# p2b-001.net
KiCad netlist of a schematic drawn in EAGLE
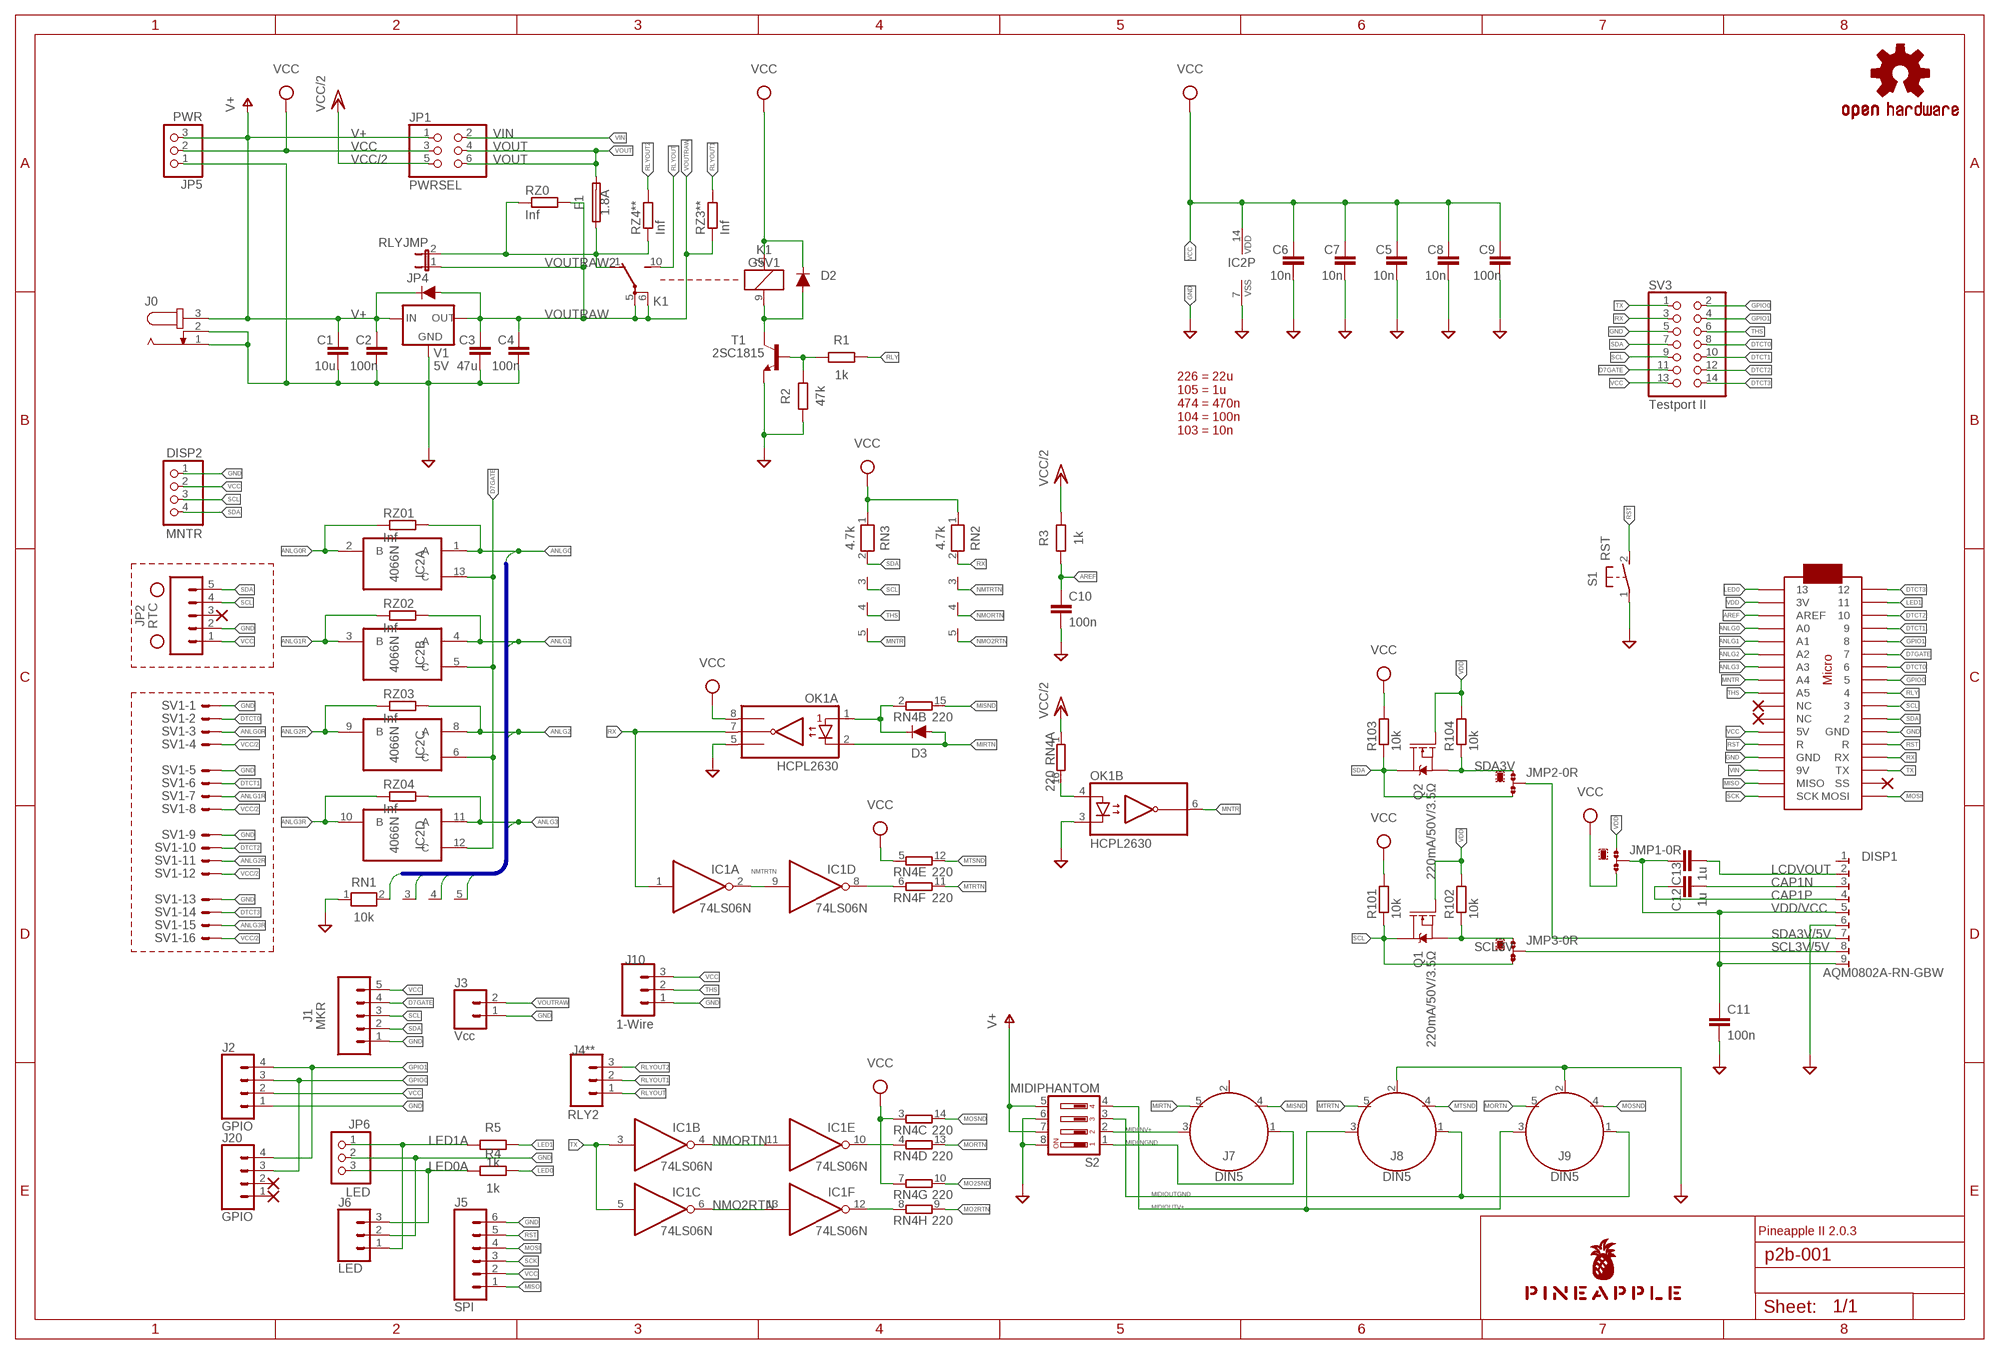
[diagram p0: schematic, sheet 1]

(export (version "E")
  (design (tool "Eeschema 10.0.6"))
  (components
    (comp (ref "C1")
      (value "10u")
      (footprint "eagle-import:C025-030X050")
      (libsource (lib "eagle-import") (part "C-EU025-030X050"))
    )
    (comp (ref "C2")
      (value "100n")
      (footprint "eagle-import:C025-024X044")
      (libsource (lib "eagle-import") (part "C-EU025-024X044"))
    )
    (comp (ref "C3")
      (value "47u")
      (footprint "eagle-import:C025-050X050")
      (libsource (lib "eagle-import") (part "C-EU025-050X050"))
    )
    (comp (ref "C4")
      (value "100n")
      (footprint "eagle-import:C025-024X044")
      (libsource (lib "eagle-import") (part "C-EU025-024X044"))
    )
    (comp (ref "C5")
      (value "10n")
      (footprint "eagle-import:C025-024X044")
      (libsource (lib "eagle-import") (part "resistor_348_C-EU025-024X044"))
    )
    (comp (ref "C6")
      (value "10n")
      (footprint "eagle-import:C025-024X044")
      (libsource (lib "eagle-import") (part "resistor_348_C-EU025-024X044"))
    )
    (comp (ref "C7")
      (value "10n")
      (footprint "eagle-import:C025-024X044")
      (libsource (lib "eagle-import") (part "resistor_348_C-EU025-024X044"))
    )
    (comp (ref "C8")
      (value "10n")
      (footprint "eagle-import:C025-024X044")
      (libsource (lib "eagle-import") (part "resistor_348_C-EU025-024X044"))
    )
    (comp (ref "C9")
      (value "100n")
      (footprint "eagle-import:C025-024X044")
      (libsource (lib "eagle-import") (part "resistor_348_C-EU025-024X044"))
    )
    (comp (ref "C10")
      (value "100n")
      (footprint "eagle-import:C025-024X044")
      (libsource (lib "eagle-import") (part "C-EU025-024X044"))
    )
    (comp (ref "C11")
      (value "100n")
      (footprint "eagle-import:C025-024X044")
      (libsource (lib "eagle-import") (part "C-EU025-024X044"))
    )
    (comp (ref "C12")
      (value "1u")
      (footprint "eagle-import:C050-024X044")
      (libsource (lib "eagle-import") (part "C-EU050-024X044"))
    )
    (comp (ref "C13")
      (value "1u")
      (footprint "eagle-import:C050-024X044")
      (libsource (lib "eagle-import") (part "C-EU050-024X044"))
    )
    (comp (ref "D1")
      (value "DIODE-1N4148")
      (footprint "eagle-import:DIODE-1N4148")
      (libsource (lib "eagle-import") (part "DIODE-1N4148"))
    )
    (comp (ref "D2")
      (value "DIODE-1N4148")
      (footprint "eagle-import:DIODE-1N4148")
      (libsource (lib "eagle-import") (part "DIODE-1N4148"))
    )
    (comp (ref "D3")
      (value "DIODE-1N4148")
      (footprint "eagle-import:DIODE-1N4148")
      (libsource (lib "eagle-import") (part "DIODE-1N4148"))
    )
    (comp (ref "DISP1")
      (value "AQM0802A-RN-GBW")
      (footprint "eagle-import:AQM0802A-RN-GBW-FOOTPRINT")
      (libsource (lib "eagle-import") (part "AQM0802A-RN-GBW"))
    )
    (comp (ref "DISP2")
      (value "MNTR")
      (footprint "eagle-import:1X04")
      (libsource (lib "eagle-import") (part "PINHD-1X4"))
    )
    (comp (ref "F1")
      (value "1.8A")
      (footprint "eagle-import:TE5")
      (libsource (lib "eagle-import") (part "TE5"))
    )
    (comp (ref "H1")
      (value "STAND-OFF")
      (footprint "eagle-import:STAND-OFF")
      (libsource (lib "eagle-import") (part "STAND-OFF"))
    )
    (comp (ref "H2")
      (value "STAND-OFF")
      (footprint "eagle-import:STAND-OFF")
      (libsource (lib "eagle-import") (part "STAND-OFF"))
    )
    (comp (ref "IC1")
      (value "74LS06N")
      (footprint "eagle-import:DIL14")
      (libsource (lib "eagle-import") (part "7406NLS"))
    )
    (comp (ref "IC2")
      (value "4066N")
      (footprint "eagle-import:DIL14")
      (libsource (lib "eagle-import") (part "4066N"))
    )
    (comp (ref "J0")
      (value "JACK-PLUG0")
      (footprint "eagle-import:SPC4077")
      (libsource (lib "eagle-import") (part "JACK-PLUG0"))
    )
    (comp (ref "J1")
      (value "MKR")
      (footprint "eagle-import:JST-5-PTH")
      (libsource (lib "eagle-import") (part "CONN_05JST"))
    )
    (comp (ref "J2")
      (value "GPIO")
      (footprint "eagle-import:JST-4-PTH")
      (libsource (lib "eagle-import") (part "CONN_04JST-PTH"))
    )
    (comp (ref "J3")
      (value "Vcc")
      (footprint "eagle-import:JST-2-PTH")
      (libsource (lib "eagle-import") (part "CONN_02JST-PTH-2"))
    )
    (comp (ref "J4**")
      (value "RLY2")
      (footprint "eagle-import:JST-3-PTH-NS")
      (libsource (lib "eagle-import") (part "CONN_03JST-PTH-NS"))
    )
    (comp (ref "J5")
      (value "SPI")
      (footprint "eagle-import:1X06_1.27MM")
      (libsource (lib "eagle-import") (part "CONN_061.27MM"))
    )
    (comp (ref "J6")
      (value "LED")
      (footprint "eagle-import:JST-3-PTH-VERT")
      (libsource (lib "eagle-import") (part "CONN_03JST-PTH-VERT"))
    )
    (comp (ref "J7")
      (value "DIN5")
      (footprint "eagle-import:DIN5-RA-PTH")
      (libsource (lib "eagle-import") (part "DIN5"))
    )
    (comp (ref "J8")
      (value "DIN5")
      (footprint "eagle-import:DIN5-RA-PTH")
      (libsource (lib "eagle-import") (part "DIN5"))
    )
    (comp (ref "J9")
      (value "DIN5")
      (footprint "eagle-import:DIN5-RA-PTH")
      (libsource (lib "eagle-import") (part "DIN5"))
    )
    (comp (ref "J10")
      (value "1-Wire")
      (footprint "eagle-import:JST-3-PTH-VERT")
      (libsource (lib "eagle-import") (part "CONN_03JST-PTH-VERT"))
    )
    (comp (ref "J20")
      (value "GPIO")
      (footprint "eagle-import:1X04_1.27MM")
      (libsource (lib "eagle-import") (part "CONN_041.27MM"))
    )
    (comp (ref "JMP1")
      (value "0R-JUMPA")
      (footprint "eagle-import:A0R-JMP")
      (libsource (lib "eagle-import") (part "0R-JUMPA"))
    )
    (comp (ref "JMP2")
      (value "0R-JUMPA")
      (footprint "eagle-import:A0R-JMP")
      (libsource (lib "eagle-import") (part "0R-JUMPA"))
    )
    (comp (ref "JMP3")
      (value "0R-JUMPA")
      (footprint "eagle-import:A0R-JMP")
      (libsource (lib "eagle-import") (part "0R-JUMPA"))
    )
    (comp (ref "JP1")
      (value "PWRSEL")
      (footprint "eagle-import:2X03")
      (libsource (lib "eagle-import") (part "PINHD-2X3"))
    )
    (comp (ref "JP2")
      (value "RTC")
      (footprint "eagle-import:1X05")
      (libsource (lib "eagle-import") (part "CONN_05"))
    )
    (comp (ref "JP4")
      (value "RLYJMP")
      (footprint "eagle-import:JP1")
      (libsource (lib "eagle-import") (part "JP1E"))
    )
    (comp (ref "JP5")
      (value "PWR")
      (footprint "eagle-import:1X03")
      (libsource (lib "eagle-import") (part "PINHD-1X3"))
    )
    (comp (ref "JP6")
      (value "LED")
      (footprint "eagle-import:1X03")
      (libsource (lib "eagle-import") (part "PINHD-1X3"))
    )
    (comp (ref "K1")
      (value "G5V1")
      (footprint "eagle-import:G5V1")
      (fields (field (name "MPN") "G5V-1-DC24"))
      (libsource (lib "eagle-import") (part "G5V1"))
    )
    (comp (ref "LOGO1")
      (value "OSHW-LOGOS-COPPER")
      (footprint "eagle-import:OSHW-LOGO-S_COPPER")
      (libsource (lib "eagle-import") (part "OSHW-LOGOS-COPPER"))
    )
    (comp (ref "MC1")
      (value "ARDUINOMICRO")
      (footprint "eagle-import:ARDUINOMICRO")
      (libsource (lib "eagle-import") (part "ARDUINOMICRO"))
    )
    (comp (ref "OK1")
      (value "HCPL2630")
      (footprint "eagle-import:DIL08")
      (fields (field (name "MF") "AGILENT TECHNOLOGIES") (field (name "MPN") "HCPL-2630-000E"))
      (libsource (lib "eagle-import") (part "HCPL2630"))
    )
    (comp (ref "Q1")
      (value "220mA/50V/3.5Ω")
      (footprint "eagle-import:SOT23-3")
      (libsource (lib "eagle-import") (part "MOSFET-NCH-BSS138"))
    )
    (comp (ref "Q2")
      (value "220mA/50V/3.5Ω")
      (footprint "eagle-import:SOT23-3")
      (libsource (lib "eagle-import") (part "MOSFET-NCH-BSS138"))
    )
    (comp (ref "R1")
      (value "1k")
      (footprint "eagle-import:0204_5")
      (libsource (lib "eagle-import") (part "resistor_348_R-EU_0204/5"))
    )
    (comp (ref "R2")
      (value "47k")
      (footprint "eagle-import:0204_5")
      (libsource (lib "eagle-import") (part "resistor_348_R-EU_0204/5"))
    )
    (comp (ref "R3")
      (value "1k")
      (footprint "eagle-import:0204_5")
      (libsource (lib "eagle-import") (part "resistor_348_R-EU_0204/5"))
    )
    (comp (ref "R4")
      (value "1k")
      (footprint "eagle-import:0204_5")
      (libsource (lib "eagle-import") (part "resistor_348_R-EU_0204/5"))
    )
    (comp (ref "R5")
      (value "1k")
      (footprint "eagle-import:0204_5")
      (libsource (lib "eagle-import") (part "resistor_348_R-EU_0204/5"))
    )
    (comp (ref "R101")
      (value "10k")
      (footprint "eagle-import:M2012")
      (libsource (lib "eagle-import") (part "R-EU_M2012"))
    )
    (comp (ref "R102")
      (value "10k")
      (footprint "eagle-import:M2012")
      (libsource (lib "eagle-import") (part "R-EU_M2012"))
    )
    (comp (ref "R103")
      (value "10k")
      (footprint "eagle-import:M2012")
      (libsource (lib "eagle-import") (part "R-EU_M2012"))
    )
    (comp (ref "R104")
      (value "10k")
      (footprint "eagle-import:M2012")
      (libsource (lib "eagle-import") (part "R-EU_M2012"))
    )
    (comp (ref "RN1")
      (value "10k")
      (footprint "eagle-import:RN-5")
      (libsource (lib "eagle-import") (part "RN04"))
    )
    (comp (ref "RN2")
      (value "4.7k")
      (footprint "eagle-import:RN-5")
      (libsource (lib "eagle-import") (part "RN04"))
    )
    (comp (ref "RN3")
      (value "4.7k")
      (footprint "eagle-import:RN-5")
      (libsource (lib "eagle-import") (part "RN04"))
    )
    (comp (ref "RN4")
      (value "220")
      (footprint "eagle-import:DIL16")
      (libsource (lib "eagle-import") (part "8R-N"))
    )
    (comp (ref "RZ0")
      (value "Inf")
      (footprint "eagle-import:M2012")
      (libsource (lib "eagle-import") (part "R-EU_M2012"))
    )
    (comp (ref "RZ01")
      (value "Inf")
      (footprint "eagle-import:M2012")
      (libsource (lib "eagle-import") (part "R-EU_M2012"))
    )
    (comp (ref "RZ02")
      (value "Inf")
      (footprint "eagle-import:M2012")
      (libsource (lib "eagle-import") (part "R-EU_M2012"))
    )
    (comp (ref "RZ03")
      (value "Inf")
      (footprint "eagle-import:M2012")
      (libsource (lib "eagle-import") (part "R-EU_M2012"))
    )
    (comp (ref "RZ3**")
      (value "Inf")
      (footprint "eagle-import:M2012")
      (libsource (lib "eagle-import") (part "R-EU_M2012"))
    )
    (comp (ref "RZ04")
      (value "Inf")
      (footprint "eagle-import:M2012")
      (libsource (lib "eagle-import") (part "R-EU_M2012"))
    )
    (comp (ref "RZ4**")
      (value "Inf")
      (footprint "eagle-import:M2012")
      (libsource (lib "eagle-import") (part "R-EU_M2012"))
    )
    (comp (ref "S1")
      (value "RST")
      (footprint "eagle-import:B3F-31XX")
      (fields (field (name "MPN") "B3F-3100"))
      (libsource (lib "eagle-import") (part "31-XX"))
    )
    (comp (ref "S2")
      (value "MIDIPHANTOM")
      (footprint "eagle-import:DIP04YL")
      (libsource (lib "eagle-import") (part "DIP04YL"))
    )
    (comp (ref "SV1")
      (value "ML16LE")
      (footprint "eagle-import:ML16L")
      (libsource (lib "eagle-import") (part "ML16LE"))
    )
    (comp (ref "SV3")
      (value "Testport II")
      (footprint "eagle-import:2X07")
      (libsource (lib "eagle-import") (part "PINHD-2X7"))
    )
    (comp (ref "T1")
      (value "2SC1815")
      (footprint "eagle-import:TO92-ECB")
      (libsource (lib "eagle-import") (part "2SC1815"))
    )
    (comp (ref "U$1")
      (value "PINEAPPLE450_SILK")
      (footprint "eagle-import:PINEAPPLE450_SILK")
      (libsource (lib "eagle-import") (part "PINEAPPLE450_SILK"))
    )
    (comp (ref "V1")
      (value "5V")
      (footprint "eagle-import:78XXS")
      (libsource (lib "eagle-import") (part "78XXS"))
    )
  )
  (nets
    (net (code "1") (name "/CAP1N") (class "Default")
      (node (ref "C12") (pin "2") (pinfunction "2_2") (pintype "passive"))
      (node (ref "DISP1") (pin "3") (pinfunction "3_3") (pintype "passive"))
    )
    (net (code "2") (name "/CAP1P") (class "Default")
      (node (ref "C12") (pin "1") (pinfunction "1_1") (pintype "passive"))
      (node (ref "DISP1") (pin "4") (pinfunction "4_4") (pintype "passive"))
    )
    (net (code "3") (name "/LCDVOUT") (class "Default")
      (node (ref "C13") (pin "2") (pinfunction "2_2") (pintype "passive"))
      (node (ref "DISP1") (pin "2") (pinfunction "2_2") (pintype "passive"))
    )
    (net (code "4") (name "/LED0A") (class "Default")
      (node (ref "J6") (pin "3") (pinfunction "3_3") (pintype "passive"))
      (node (ref "JP6") (pin "3") (pinfunction "3_3") (pintype "passive"))
      (node (ref "R4") (pin "1") (pinfunction "1_1") (pintype "passive"))
    )
    (net (code "5") (name "/LED1A") (class "Default")
      (node (ref "J6") (pin "1") (pinfunction "1_1") (pintype "passive"))
      (node (ref "JP6") (pin "1") (pinfunction "1_1") (pintype "passive"))
      (node (ref "R5") (pin "1") (pinfunction "1_1") (pintype "passive"))
    )
    (net (code "6") (name "/MIDIINGND") (class "Default")
      (node (ref "J7") (pin "1") (pinfunction "1_1") (pintype "bidirectional"))
      (node (ref "S2") (pin "1") (pinfunction "1_1") (pintype "passive"))
    )
    (net (code "7") (name "/MIDIINV+") (class "Default")
      (node (ref "J7") (pin "3") (pinfunction "3_3") (pintype "bidirectional"))
      (node (ref "S2") (pin "2") (pinfunction "2_2") (pintype "passive"))
    )
    (net (code "8") (name "/MIDIOUTGND") (class "Default")
      (node (ref "J8") (pin "1") (pinfunction "1_1") (pintype "bidirectional"))
      (node (ref "J9") (pin "1") (pinfunction "1_1") (pintype "bidirectional"))
      (node (ref "S2") (pin "3") (pinfunction "3_3") (pintype "passive"))
    )
    (net (code "9") (name "/MIDIOUTV+") (class "Default")
      (node (ref "J8") (pin "3") (pinfunction "3_3") (pintype "bidirectional"))
      (node (ref "J9") (pin "3") (pinfunction "3_3") (pintype "bidirectional"))
      (node (ref "S2") (pin "4") (pinfunction "4_4") (pintype "passive"))
    )
    (net (code "10") (name "/SCL3V") (class "Default")
      (node (ref "JMP3") (pin "1") (pinfunction "1_1") (pintype "passive"))
      (node (ref "Q1") (pin "2") (pinfunction "S_2") (pintype "bidirectional"))
      (node (ref "R102") (pin "1") (pinfunction "1_1") (pintype "passive"))
    )
    (net (code "11") (name "/SCL3V{slash}5V") (class "Default")
      (node (ref "DISP1") (pin "8") (pinfunction "8_8") (pintype "passive"))
      (node (ref "JMP3") (pin "2") (pinfunction "2_2") (pintype "passive"))
    )
    (net (code "12") (name "/SDA3V") (class "Default")
      (node (ref "JMP2") (pin "1") (pinfunction "1_1") (pintype "passive"))
      (node (ref "Q2") (pin "2") (pinfunction "S_2") (pintype "bidirectional"))
      (node (ref "R104") (pin "1") (pinfunction "1_1") (pintype "passive"))
    )
    (net (code "13") (name "/SDA3V{slash}5V") (class "Default")
      (node (ref "DISP1") (pin "7") (pinfunction "7_7") (pintype "passive"))
      (node (ref "JMP2") (pin "2") (pinfunction "2_2") (pintype "passive"))
    )
    (net (code "14") (name "/VDD{slash}VCC") (class "Default")
      (node (ref "C11") (pin "1") (pinfunction "1_1") (pintype "passive"))
      (node (ref "C13") (pin "1") (pinfunction "1_1") (pintype "passive"))
      (node (ref "DISP1") (pin "5") (pinfunction "5_5") (pintype "passive"))
      (node (ref "DISP1") (pin "9") (pinfunction "9_9") (pintype "passive"))
      (node (ref "JMP1") (pin "2") (pinfunction "2_2") (pintype "passive"))
    )
    (net (code "15") (name "/VOUTRAW2") (class "Default")
      (node (ref "F1") (pin "1") (pinfunction "1_1") (pintype "passive"))
      (node (ref "JP4") (pin "2") (pinfunction "2_2") (pintype "passive"))
      (node (ref "K1") (pin "1") (pinfunction "O_1") (pintype "passive"))
      (node (ref "RZ0") (pin "1") (pinfunction "1_1") (pintype "passive"))
      (node (ref "RZ4**") (pin "1") (pinfunction "1_1") (pintype "passive"))
    )
    (net (code "16") (name "ANLG0") (class "Default")
      (node (ref "IC2") (pin "1") (pinfunction "A_1") (pintype "tri_state"))
      (node (ref "MC1") (pin "P$31") (pinfunction "A0_P$31") (pintype "bidirectional"))
      (node (ref "RN1") (pin "2") (pinfunction "2_2") (pintype "passive"))
      (node (ref "RZ01") (pin "2") (pinfunction "2_2") (pintype "passive"))
    )
    (net (code "17") (name "ANLG0R") (class "Default")
      (node (ref "IC2") (pin "2") (pinfunction "B_2") (pintype "tri_state"))
      (node (ref "RZ01") (pin "1") (pinfunction "1_1") (pintype "passive"))
      (node (ref "SV1") (pin "3") (pinfunction "S_3") (pintype "passive"))
    )
    (net (code "18") (name "ANLG1") (class "Default")
      (node (ref "IC2") (pin "4") (pinfunction "A_4") (pintype "tri_state"))
      (node (ref "MC1") (pin "P$30") (pinfunction "A1_P$30") (pintype "bidirectional"))
      (node (ref "RN1") (pin "3") (pinfunction "3_3") (pintype "passive"))
      (node (ref "RZ02") (pin "2") (pinfunction "2_2") (pintype "passive"))
    )
    (net (code "19") (name "ANLG1R") (class "Default")
      (node (ref "IC2") (pin "3") (pinfunction "B_3") (pintype "tri_state"))
      (node (ref "RZ02") (pin "1") (pinfunction "1_1") (pintype "passive"))
      (node (ref "SV1") (pin "7") (pinfunction "S_7") (pintype "passive"))
    )
    (net (code "20") (name "ANLG2") (class "Default")
      (node (ref "IC2") (pin "8") (pinfunction "A_8") (pintype "tri_state"))
      (node (ref "MC1") (pin "P$29") (pinfunction "A2_P$29") (pintype "bidirectional"))
      (node (ref "RN1") (pin "4") (pinfunction "4_4") (pintype "passive"))
      (node (ref "RZ03") (pin "2") (pinfunction "2_2") (pintype "passive"))
    )
    (net (code "21") (name "ANLG2R") (class "Default")
      (node (ref "IC2") (pin "9") (pinfunction "B_9") (pintype "tri_state"))
      (node (ref "RZ03") (pin "1") (pinfunction "1_1") (pintype "passive"))
      (node (ref "SV1") (pin "11") (pinfunction "S_11") (pintype "passive"))
    )
    (net (code "22") (name "ANLG3") (class "Default")
      (node (ref "IC2") (pin "11") (pinfunction "A_11") (pintype "tri_state"))
      (node (ref "MC1") (pin "P$28") (pinfunction "A3_P$28") (pintype "bidirectional"))
      (node (ref "RN1") (pin "5") (pinfunction "5_5") (pintype "passive"))
      (node (ref "RZ04") (pin "2") (pinfunction "2_2") (pintype "passive"))
    )
    (net (code "23") (name "ANLG3R") (class "Default")
      (node (ref "IC2") (pin "10") (pinfunction "B_10") (pintype "tri_state"))
      (node (ref "RZ04") (pin "1") (pinfunction "1_1") (pintype "passive"))
      (node (ref "SV1") (pin "15") (pinfunction "S_15") (pintype "passive"))
    )
    (net (code "24") (name "AREF") (class "Default")
      (node (ref "C10") (pin "1") (pinfunction "1_1") (pintype "passive"))
      (node (ref "MC1") (pin "P$32") (pinfunction "AREF_P$32") (pintype "bidirectional"))
      (node (ref "R3") (pin "1") (pinfunction "1_1") (pintype "passive"))
    )
    (net (code "25") (name "D7GATE") (class "Default")
      (node (ref "IC2") (pin "12") (pinfunction "C_12") (pintype "input"))
      (node (ref "IC2") (pin "13") (pinfunction "C_13") (pintype "input"))
      (node (ref "IC2") (pin "5") (pinfunction "C_5") (pintype "input"))
      (node (ref "IC2") (pin "6") (pinfunction "C_6") (pintype "input"))
      (node (ref "J1") (pin "4") (pinfunction "4_4") (pintype "passive"))
      (node (ref "MC1") (pin "P$6") (pinfunction "7_P$6") (pintype "bidirectional"))
      (node (ref "SV3") (pin "11") (pinfunction "11_11") (pintype "passive"))
    )
    (net (code "26") (name "DTCT0") (class "Default")
      (node (ref "MC1") (pin "P$7") (pinfunction "6_P$7") (pintype "bidirectional"))
      (node (ref "SV1") (pin "2") (pinfunction "S_2") (pintype "passive"))
      (node (ref "SV3") (pin "8") (pinfunction "8_8") (pintype "passive"))
    )
    (net (code "27") (name "DTCT1") (class "Default")
      (node (ref "MC1") (pin "P$4") (pinfunction "9_P$4") (pintype "bidirectional"))
      (node (ref "SV1") (pin "6") (pinfunction "S_6") (pintype "passive"))
      (node (ref "SV3") (pin "10") (pinfunction "10_10") (pintype "passive"))
    )
    (net (code "28") (name "DTCT2") (class "Default")
      (node (ref "MC1") (pin "P$3") (pinfunction "10_P$3") (pintype "bidirectional"))
      (node (ref "SV1") (pin "10") (pinfunction "S_10") (pintype "passive"))
      (node (ref "SV3") (pin "12") (pinfunction "12_12") (pintype "passive"))
    )
    (net (code "29") (name "DTCT3") (class "Default")
      (node (ref "MC1") (pin "P$1") (pinfunction "12_P$1") (pintype "bidirectional"))
      (node (ref "SV1") (pin "14") (pinfunction "S_14") (pintype "passive"))
      (node (ref "SV3") (pin "14") (pinfunction "14_14") (pintype "passive"))
    )
    (net (code "30") (name "GND") (class "Default")
      (node (ref "C1") (pin "2") (pinfunction "2_2") (pintype "passive"))
      (node (ref "C10") (pin "2") (pinfunction "2_2") (pintype "passive"))
      (node (ref "C11") (pin "2") (pinfunction "2_2") (pintype "passive"))
      (node (ref "C2") (pin "2") (pinfunction "2_2") (pintype "passive"))
      (node (ref "C3") (pin "2") (pinfunction "2_2") (pintype "passive"))
      (node (ref "C4") (pin "2") (pinfunction "2_2") (pintype "passive"))
      (node (ref "C5") (pin "2") (pinfunction "2_2") (pintype "passive"))
      (node (ref "C6") (pin "2") (pinfunction "2_2") (pintype "passive"))
      (node (ref "C7") (pin "2") (pinfunction "2_2") (pintype "passive"))
      (node (ref "C8") (pin "2") (pinfunction "2_2") (pintype "passive"))
      (node (ref "C9") (pin "2") (pinfunction "2_2") (pintype "passive"))
      (node (ref "DISP1") (pin "6") (pinfunction "6_6") (pintype "passive"))
      (node (ref "DISP2") (pin "1") (pinfunction "1_1") (pintype "passive"))
      (node (ref "IC2") (pin "7") (pinfunction "VSS_7") (pintype "power_in"))
      (node (ref "J0") (pin "1") (pinfunction "1_1") (pintype "passive"))
      (node (ref "J0") (pin "2") (pinfunction "2_2") (pintype "passive"))
      (node (ref "J1") (pin "1") (pinfunction "1_1") (pintype "passive"))
      (node (ref "J10") (pin "1") (pinfunction "1_1") (pintype "passive"))
      (node (ref "J2") (pin "1") (pinfunction "1_1") (pintype "passive"))
      (node (ref "J3") (pin "1") (pinfunction "1_1") (pintype "passive"))
      (node (ref "J5") (pin "6") (pinfunction "6_6") (pintype "passive"))
      (node (ref "J6") (pin "2") (pinfunction "2_2") (pintype "passive"))
      (node (ref "J8") (pin "2") (pinfunction "2_2") (pintype "bidirectional"))
      (node (ref "J9") (pin "2") (pinfunction "2_2") (pintype "bidirectional"))
      (node (ref "JP2") (pin "2") (pinfunction "2_2") (pintype "passive"))
      (node (ref "JP5") (pin "1") (pinfunction "1_1") (pintype "passive"))
      (node (ref "JP6") (pin "2") (pinfunction "2_2") (pintype "passive"))
      (node (ref "MC1") (pin "P$12") (pinfunction "GND_P$12") (pintype "bidirectional"))
      (node (ref "MC1") (pin "P$21") (pinfunction "GND_P$21") (pintype "bidirectional"))
      (node (ref "OK1") (pin "3") (pinfunction "C2_3") (pintype "passive"))
      (node (ref "OK1") (pin "5") (pinfunction "GND_5") (pintype "passive"))
      (node (ref "R2") (pin "1") (pinfunction "1_1") (pintype "passive"))
      (node (ref "RN1") (pin "1") (pinfunction "1_1") (pintype "passive"))
      (node (ref "S1") (pin "1") (pinfunction "P_1") (pintype "passive"))
      (node (ref "S2") (pin "6") (pinfunction "6_6") (pintype "passive"))
      (node (ref "S2") (pin "8") (pinfunction "8_8") (pintype "passive"))
      (node (ref "SV1") (pin "1") (pinfunction "S_1") (pintype "passive"))
      (node (ref "SV1") (pin "13") (pinfunction "S_13") (pintype "passive"))
      (node (ref "SV1") (pin "5") (pinfunction "S_5") (pintype "passive"))
      (node (ref "SV1") (pin "9") (pinfunction "S_9") (pintype "passive"))
      (node (ref "SV3") (pin "5") (pinfunction "5_5") (pintype "passive"))
      (node (ref "T1") (pin "E") (pinfunction "E_E") (pintype "passive"))
      (node (ref "V1") (pin "GND") (pinfunction "GND_GND") (pintype "input"))
    )
    (net (code "31") (name "GPIO0") (class "Default")
      (node (ref "J2") (pin "3") (pinfunction "3_3") (pintype "passive"))
      (node (ref "J20") (pin "3") (pinfunction "3_3") (pintype "passive"))
      (node (ref "MC1") (pin "P$8") (pinfunction "5_P$8") (pintype "bidirectional"))
      (node (ref "SV3") (pin "2") (pinfunction "2_2") (pintype "passive"))
    )
    (net (code "32") (name "GPIO1") (class "Default")
      (node (ref "J2") (pin "4") (pinfunction "4_4") (pintype "passive"))
      (node (ref "J20") (pin "4") (pinfunction "4_4") (pintype "passive"))
      (node (ref "MC1") (pin "P$5") (pinfunction "8_P$5") (pintype "bidirectional"))
      (node (ref "SV3") (pin "4") (pinfunction "4_4") (pintype "passive"))
    )
    (net (code "33") (name "LED0") (class "Default")
      (node (ref "MC1") (pin "P$34") (pinfunction "13_P$34") (pintype "bidirectional"))
      (node (ref "R4") (pin "2") (pinfunction "2_2") (pintype "passive"))
    )
    (net (code "34") (name "LED1") (class "Default")
      (node (ref "MC1") (pin "P$2") (pinfunction "11_P$2") (pintype "bidirectional"))
      (node (ref "R5") (pin "2") (pinfunction "2_2") (pintype "passive"))
    )
    (net (code "35") (name "MIRTN") (class "Default")
      (node (ref "D3") (pin "A") (pinfunction "A_A") (pintype "passive"))
      (node (ref "J7") (pin "5") (pinfunction "5_5") (pintype "bidirectional"))
      (node (ref "OK1") (pin "2") (pinfunction "C1_2") (pintype "passive"))
    )
    (net (code "36") (name "MISND") (class "Default")
      (node (ref "J7") (pin "4") (pinfunction "4_4") (pintype "bidirectional"))
      (node (ref "RN4") (pin "15") (pinfunction "2_15") (pintype "passive"))
    )
    (net (code "37") (name "MISO") (class "Default")
      (node (ref "J5") (pin "1") (pinfunction "1_1") (pintype "passive"))
      (node (ref "MC1") (pin "P$19") (pinfunction "MISO_P$19") (pintype "bidirectional"))
    )
    (net (code "38") (name "MNTR") (class "Default")
      (node (ref "MC1") (pin "P$27") (pinfunction "A4_P$27") (pintype "bidirectional"))
      (node (ref "OK1") (pin "6") (pinfunction "VO2_6") (pintype "passive"))
      (node (ref "RN3") (pin "5") (pinfunction "5_5") (pintype "passive"))
    )
    (net (code "39") (name "MO2RTN") (class "Default")
      (node (ref "RN4") (pin "9") (pinfunction "2_9") (pintype "passive"))
    )
    (net (code "40") (name "MO2SND") (class "Default")
      (node (ref "RN4") (pin "10") (pinfunction "2_10") (pintype "passive"))
    )
    (net (code "41") (name "MORTN") (class "Default")
      (node (ref "J9") (pin "5") (pinfunction "5_5") (pintype "bidirectional"))
      (node (ref "RN4") (pin "13") (pinfunction "2_13") (pintype "passive"))
    )
    (net (code "42") (name "MOSI") (class "Default")
      (node (ref "J5") (pin "4") (pinfunction "4_4") (pintype "passive"))
      (node (ref "MC1") (pin "P$17") (pinfunction "MOSI_P$17") (pintype "bidirectional"))
    )
    (net (code "43") (name "MOSND") (class "Default")
      (node (ref "J9") (pin "4") (pinfunction "4_4") (pintype "bidirectional"))
      (node (ref "RN4") (pin "14") (pinfunction "2_14") (pintype "passive"))
    )
    (net (code "44") (name "MTRTN") (class "Default")
      (node (ref "J8") (pin "5") (pinfunction "5_5") (pintype "bidirectional"))
      (node (ref "RN4") (pin "11") (pinfunction "2_11") (pintype "passive"))
    )
    (net (code "45") (name "MTSND") (class "Default")
      (node (ref "J8") (pin "4") (pinfunction "4_4") (pintype "bidirectional"))
      (node (ref "RN4") (pin "12") (pinfunction "2_12") (pintype "passive"))
    )
    (net (code "46") (name "NMO2RTN") (class "Default")
      (node (ref "IC1") (pin "13") (pinfunction "I_13") (pintype "input"))
      (node (ref "IC1") (pin "6") (pinfunction "O_6") (pintype "open_collector"))
      (node (ref "RN2") (pin "5") (pinfunction "5_5") (pintype "passive"))
    )
    (net (code "47") (name "NMORTN") (class "Default")
      (node (ref "IC1") (pin "11") (pinfunction "I_11") (pintype "input"))
      (node (ref "IC1") (pin "4") (pinfunction "O_4") (pintype "open_collector"))
      (node (ref "RN2") (pin "4") (pinfunction "4_4") (pintype "passive"))
    )
    (net (code "48") (name "NMTRTN") (class "Default")
      (node (ref "IC1") (pin "2") (pinfunction "O_2") (pintype "open_collector"))
      (node (ref "IC1") (pin "9") (pinfunction "I_9") (pintype "input"))
      (node (ref "RN2") (pin "3") (pinfunction "3_3") (pintype "passive"))
    )
    (net (code "49") (name "Net-(IC1D-O)") (class "Default")
      (node (ref "IC1") (pin "8") (pinfunction "O_8") (pintype "open_collector"))
      (node (ref "RN4") (pin "6") (pinfunction "1_6") (pintype "passive"))
    )
    (net (code "50") (name "Net-(IC1E-O)") (class "Default")
      (node (ref "IC1") (pin "10") (pinfunction "O_10") (pintype "open_collector"))
      (node (ref "RN4") (pin "4") (pinfunction "1_4") (pintype "passive"))
    )
    (net (code "51") (name "Net-(IC1F-O)") (class "Default")
      (node (ref "IC1") (pin "12") (pinfunction "O_12") (pintype "open_collector"))
      (node (ref "RN4") (pin "8") (pinfunction "1_8") (pintype "passive"))
    )
    (net (code "52") (name "Net-(K1A-2)") (class "Default")
      (node (ref "D2") (pin "A") (pinfunction "A_A") (pintype "passive"))
      (node (ref "K1") (pin "9") (pinfunction "2_9") (pintype "passive"))
      (node (ref "T1") (pin "C") (pinfunction "C_C") (pintype "passive"))
    )
    (net (code "53") (name "Net-(OK1A-A1)") (class "Default")
      (node (ref "D3") (pin "C") (pinfunction "C_C") (pintype "passive"))
      (node (ref "OK1") (pin "1") (pinfunction "A1_1") (pintype "passive"))
      (node (ref "RN4") (pin "2") (pinfunction "1_2") (pintype "passive"))
    )
    (net (code "54") (name "Net-(OK1B-A2)") (class "Default")
      (node (ref "OK1") (pin "4") (pinfunction "A2_4") (pintype "passive"))
      (node (ref "RN4") (pin "16") (pinfunction "2_16") (pintype "passive"))
    )
    (net (code "55") (name "Net-(R1-Pad1)") (class "Default")
      (node (ref "R1") (pin "1") (pinfunction "1_1") (pintype "passive"))
      (node (ref "R2") (pin "2") (pinfunction "2_2") (pintype "passive"))
      (node (ref "T1") (pin "B") (pinfunction "B_B") (pintype "passive"))
    )
    (net (code "56") (name "RLY") (class "Default")
      (node (ref "MC1") (pin "P$9") (pinfunction "4_P$9") (pintype "bidirectional"))
      (node (ref "R1") (pin "2") (pinfunction "2_2") (pintype "passive"))
    )
    (net (code "57") (name "RLYOUT") (class "Default")
      (node (ref "J4**") (pin "1") (pinfunction "1_1") (pintype "passive"))
      (node (ref "K1") (pin "10") (pinfunction "S_10") (pintype "passive"))
    )
    (net (code "58") (name "RLYOUT1") (class "Default")
      (node (ref "J4**") (pin "2") (pinfunction "2_2") (pintype "passive"))
      (node (ref "RZ3**") (pin "2") (pinfunction "2_2") (pintype "passive"))
    )
    (net (code "59") (name "RLYOUT2") (class "Default")
      (node (ref "J4**") (pin "3") (pinfunction "3_3") (pintype "passive"))
      (node (ref "RZ4**") (pin "2") (pinfunction "2_2") (pintype "passive"))
    )
    (net (code "60") (name "RST") (class "Default")
      (node (ref "J5") (pin "5") (pinfunction "5_5") (pintype "passive"))
      (node (ref "MC1") (pin "P$13") (pinfunction "R_P$13") (pintype "bidirectional"))
      (node (ref "MC1") (pin "P$22") (pinfunction "R_P$22") (pintype "bidirectional"))
      (node (ref "S1") (pin "2") (pinfunction "S_2") (pintype "passive"))
    )
    (net (code "61") (name "RX") (class "Default")
      (node (ref "IC1") (pin "1") (pinfunction "I_1") (pintype "input"))
      (node (ref "MC1") (pin "P$14") (pinfunction "RX_P$14") (pintype "bidirectional"))
      (node (ref "OK1") (pin "7") (pinfunction "VO1_7") (pintype "passive"))
      (node (ref "RN2") (pin "2") (pinfunction "2_2") (pintype "passive"))
      (node (ref "SV3") (pin "3") (pinfunction "3_3") (pintype "passive"))
    )
    (net (code "62") (name "SCK") (class "Default")
      (node (ref "J5") (pin "3") (pinfunction "3_3") (pintype "passive"))
      (node (ref "MC1") (pin "P$18") (pinfunction "SCK_P$18") (pintype "bidirectional"))
    )
    (net (code "63") (name "SCL") (class "Default")
      (node (ref "DISP2") (pin "3") (pinfunction "3_3") (pintype "passive"))
      (node (ref "J1") (pin "3") (pinfunction "3_3") (pintype "passive"))
      (node (ref "JMP3") (pin "3") (pinfunction "3_3") (pintype "passive"))
      (node (ref "JP2") (pin "4") (pinfunction "4_4") (pintype "passive"))
      (node (ref "MC1") (pin "P$10") (pinfunction "3_P$10") (pintype "bidirectional"))
      (node (ref "Q1") (pin "3") (pinfunction "D_3") (pintype "bidirectional"))
      (node (ref "R101") (pin "1") (pinfunction "1_1") (pintype "passive"))
      (node (ref "RN3") (pin "3") (pinfunction "3_3") (pintype "passive"))
      (node (ref "SV3") (pin "9") (pinfunction "9_9") (pintype "passive"))
    )
    (net (code "64") (name "SDA") (class "Default")
      (node (ref "DISP2") (pin "4") (pinfunction "4_4") (pintype "passive"))
      (node (ref "J1") (pin "2") (pinfunction "2_2") (pintype "passive"))
      (node (ref "JMP2") (pin "3") (pinfunction "3_3") (pintype "passive"))
      (node (ref "JP2") (pin "5") (pinfunction "5_5") (pintype "passive"))
      (node (ref "MC1") (pin "P$11") (pinfunction "2_P$11") (pintype "bidirectional"))
      (node (ref "Q2") (pin "3") (pinfunction "D_3") (pintype "bidirectional"))
      (node (ref "R103") (pin "1") (pinfunction "1_1") (pintype "passive"))
      (node (ref "RN3") (pin "2") (pinfunction "2_2") (pintype "passive"))
      (node (ref "SV3") (pin "7") (pinfunction "7_7") (pintype "passive"))
    )
    (net (code "65") (name "THS") (class "Default")
      (node (ref "J10") (pin "2") (pinfunction "2_2") (pintype "passive"))
      (node (ref "MC1") (pin "P$26") (pinfunction "A5_P$26") (pintype "bidirectional"))
      (node (ref "RN3") (pin "4") (pinfunction "4_4") (pintype "passive"))
      (node (ref "SV3") (pin "6") (pinfunction "6_6") (pintype "passive"))
    )
    (net (code "66") (name "TX") (class "Default")
      (node (ref "IC1") (pin "3") (pinfunction "I_3") (pintype "input"))
      (node (ref "IC1") (pin "5") (pinfunction "I_5") (pintype "input"))
      (node (ref "MC1") (pin "P$15") (pinfunction "TX_P$15") (pintype "bidirectional"))
      (node (ref "SV3") (pin "1") (pinfunction "1_1") (pintype "passive"))
    )
    (net (code "67") (name "V+") (class "Default")
      (node (ref "C1") (pin "1") (pinfunction "1_1") (pintype "passive"))
      (node (ref "C2") (pin "1") (pinfunction "1_1") (pintype "passive"))
      (node (ref "D1") (pin "C") (pinfunction "C_C") (pintype "passive"))
      (node (ref "J0") (pin "3") (pinfunction "3_3") (pintype "passive"))
      (node (ref "JP1") (pin "1") (pinfunction "1_1") (pintype "passive"))
      (node (ref "JP5") (pin "3") (pinfunction "3_3") (pintype "passive"))
      (node (ref "S2") (pin "5") (pinfunction "5_5") (pintype "passive"))
      (node (ref "S2") (pin "7") (pinfunction "7_7") (pintype "passive"))
      (node (ref "V1") (pin "IN") (pinfunction "IN_IN") (pintype "input"))
    )
    (net (code "68") (name "VCC") (class "Default")
      (node (ref "C5") (pin "1") (pinfunction "1_1") (pintype "passive"))
      (node (ref "C6") (pin "1") (pinfunction "1_1") (pintype "passive"))
      (node (ref "C7") (pin "1") (pinfunction "1_1") (pintype "passive"))
      (node (ref "C8") (pin "1") (pinfunction "1_1") (pintype "passive"))
      (node (ref "C9") (pin "1") (pinfunction "1_1") (pintype "passive"))
      (node (ref "D2") (pin "C") (pinfunction "C_C") (pintype "passive"))
      (node (ref "DISP2") (pin "2") (pinfunction "2_2") (pintype "passive"))
      (node (ref "IC2") (pin "14") (pinfunction "VDD_14") (pintype "power_in"))
      (node (ref "J1") (pin "5") (pinfunction "5_5") (pintype "passive"))
      (node (ref "J10") (pin "3") (pinfunction "3_3") (pintype "passive"))
      (node (ref "J2") (pin "2") (pinfunction "2_2") (pintype "passive"))
      (node (ref "J5") (pin "2") (pinfunction "2_2") (pintype "passive"))
      (node (ref "JMP1") (pin "3") (pinfunction "3_3") (pintype "passive"))
      (node (ref "JP1") (pin "3") (pinfunction "3_3") (pintype "passive"))
      (node (ref "JP2") (pin "1") (pinfunction "1_1") (pintype "passive"))
      (node (ref "JP5") (pin "2") (pinfunction "2_2") (pintype "passive"))
      (node (ref "K1") (pin "2") (pinfunction "1_2") (pintype "passive"))
      (node (ref "MC1") (pin "P$23") (pinfunction "5V_P$23") (pintype "bidirectional"))
      (node (ref "OK1") (pin "8") (pinfunction "VCC_8") (pintype "passive"))
      (node (ref "R101") (pin "2") (pinfunction "2_2") (pintype "passive"))
      (node (ref "R103") (pin "2") (pinfunction "2_2") (pintype "passive"))
      (node (ref "RN2") (pin "1") (pinfunction "1_1") (pintype "passive"))
      (node (ref "RN3") (pin "1") (pinfunction "1_1") (pintype "passive"))
      (node (ref "RN4") (pin "3") (pinfunction "1_3") (pintype "passive"))
      (node (ref "RN4") (pin "5") (pinfunction "1_5") (pintype "passive"))
      (node (ref "RN4") (pin "7") (pinfunction "1_7") (pintype "passive"))
      (node (ref "SV3") (pin "13") (pinfunction "13_13") (pintype "passive"))
    )
    (net (code "69") (name "VCC{slash}2") (class "Default")
      (node (ref "JP1") (pin "5") (pinfunction "5_5") (pintype "passive"))
      (node (ref "R3") (pin "2") (pinfunction "2_2") (pintype "passive"))
      (node (ref "RN4") (pin "1") (pinfunction "1_1") (pintype "passive"))
      (node (ref "SV1") (pin "12") (pinfunction "S_12") (pintype "passive"))
      (node (ref "SV1") (pin "16") (pinfunction "S_16") (pintype "passive"))
      (node (ref "SV1") (pin "4") (pinfunction "S_4") (pintype "passive"))
      (node (ref "SV1") (pin "8") (pinfunction "S_8") (pintype "passive"))
    )
    (net (code "70") (name "VDD") (class "Default")
      (node (ref "JMP1") (pin "1") (pinfunction "1_1") (pintype "passive"))
      (node (ref "MC1") (pin "P$33") (pinfunction "3V_P$33") (pintype "bidirectional"))
      (node (ref "Q1") (pin "1") (pinfunction "G_1") (pintype "bidirectional"))
      (node (ref "Q2") (pin "1") (pinfunction "G_1") (pintype "bidirectional"))
      (node (ref "R102") (pin "2") (pinfunction "2_2") (pintype "passive"))
      (node (ref "R104") (pin "2") (pinfunction "2_2") (pintype "passive"))
    )
    (net (code "71") (name "VIN") (class "Default")
      (node (ref "JP1") (pin "2") (pinfunction "2_2") (pintype "passive"))
      (node (ref "MC1") (pin "P$20") (pinfunction "9V_P$20") (pintype "bidirectional"))
    )
    (net (code "72") (name "VOUT") (class "Default")
      (node (ref "F1") (pin "2") (pinfunction "2_2") (pintype "passive"))
      (node (ref "JP1") (pin "4") (pinfunction "4_4") (pintype "passive"))
      (node (ref "JP1") (pin "6") (pinfunction "6_6") (pintype "passive"))
    )
    (net (code "73") (name "VOUTRAW") (class "Default")
      (node (ref "C3") (pin "1") (pinfunction "1_1") (pintype "passive"))
      (node (ref "C4") (pin "1") (pinfunction "1_1") (pintype "passive"))
      (node (ref "D1") (pin "A") (pinfunction "A_A") (pintype "passive"))
      (node (ref "J3") (pin "2") (pinfunction "2_2") (pintype "passive"))
      (node (ref "JP4") (pin "1") (pinfunction "1_1") (pintype "passive"))
      (node (ref "K1") (pin "5") (pinfunction "P_5") (pintype "passive"))
      (node (ref "K1") (pin "6") (pinfunction "P_6") (pintype "passive"))
      (node (ref "RZ0") (pin "2") (pinfunction "2_2") (pintype "passive"))
      (node (ref "RZ3**") (pin "1") (pinfunction "1_1") (pintype "passive"))
      (node (ref "V1") (pin "OUT") (pinfunction "OUT_OUT") (pintype "passive"))
    )
    (net (code "74") (name "unconnected-(DISP1-Pad1)") (class "Default")
      (node (ref "DISP1") (pin "1") (pinfunction "1_1") (pintype "passive"))
    )
    (net (code "75") (name "unconnected-(J7-Pad2)") (class "Default")
      (node (ref "J7") (pin "2") (pinfunction "2_2") (pintype "bidirectional"))
    )
    (net (code "76") (name "unconnected-(J20-Pad1)") (class "Default")
      (node (ref "J20") (pin "1") (pinfunction "1_1") (pintype "passive"))
    )
    (net (code "77") (name "unconnected-(J20-Pad2)") (class "Default")
      (node (ref "J20") (pin "2") (pinfunction "2_2") (pintype "passive"))
    )
    (net (code "78") (name "unconnected-(JP2-Pad3)") (class "Default")
      (node (ref "JP2") (pin "3") (pinfunction "3_3") (pintype "passive"))
    )
    (net (code "79") (name "unconnected-(MC1-NC-PadP$24)") (class "Default")
      (node (ref "MC1") (pin "P$24") (pinfunction "NC_P$24") (pintype "bidirectional"))
    )
    (net (code "80") (name "unconnected-(MC1-NC-PadP$25)") (class "Default")
      (node (ref "MC1") (pin "P$25") (pinfunction "NC_P$25") (pintype "bidirectional"))
    )
    (net (code "81") (name "unconnected-(MC1-SS-PadP$16)") (class "Default")
      (node (ref "MC1") (pin "P$16") (pinfunction "SS_P$16") (pintype "bidirectional"))
    )
  )
)
